# Power_PMIC.net
KiCad netlist of a schematic drawn in Altium Designer
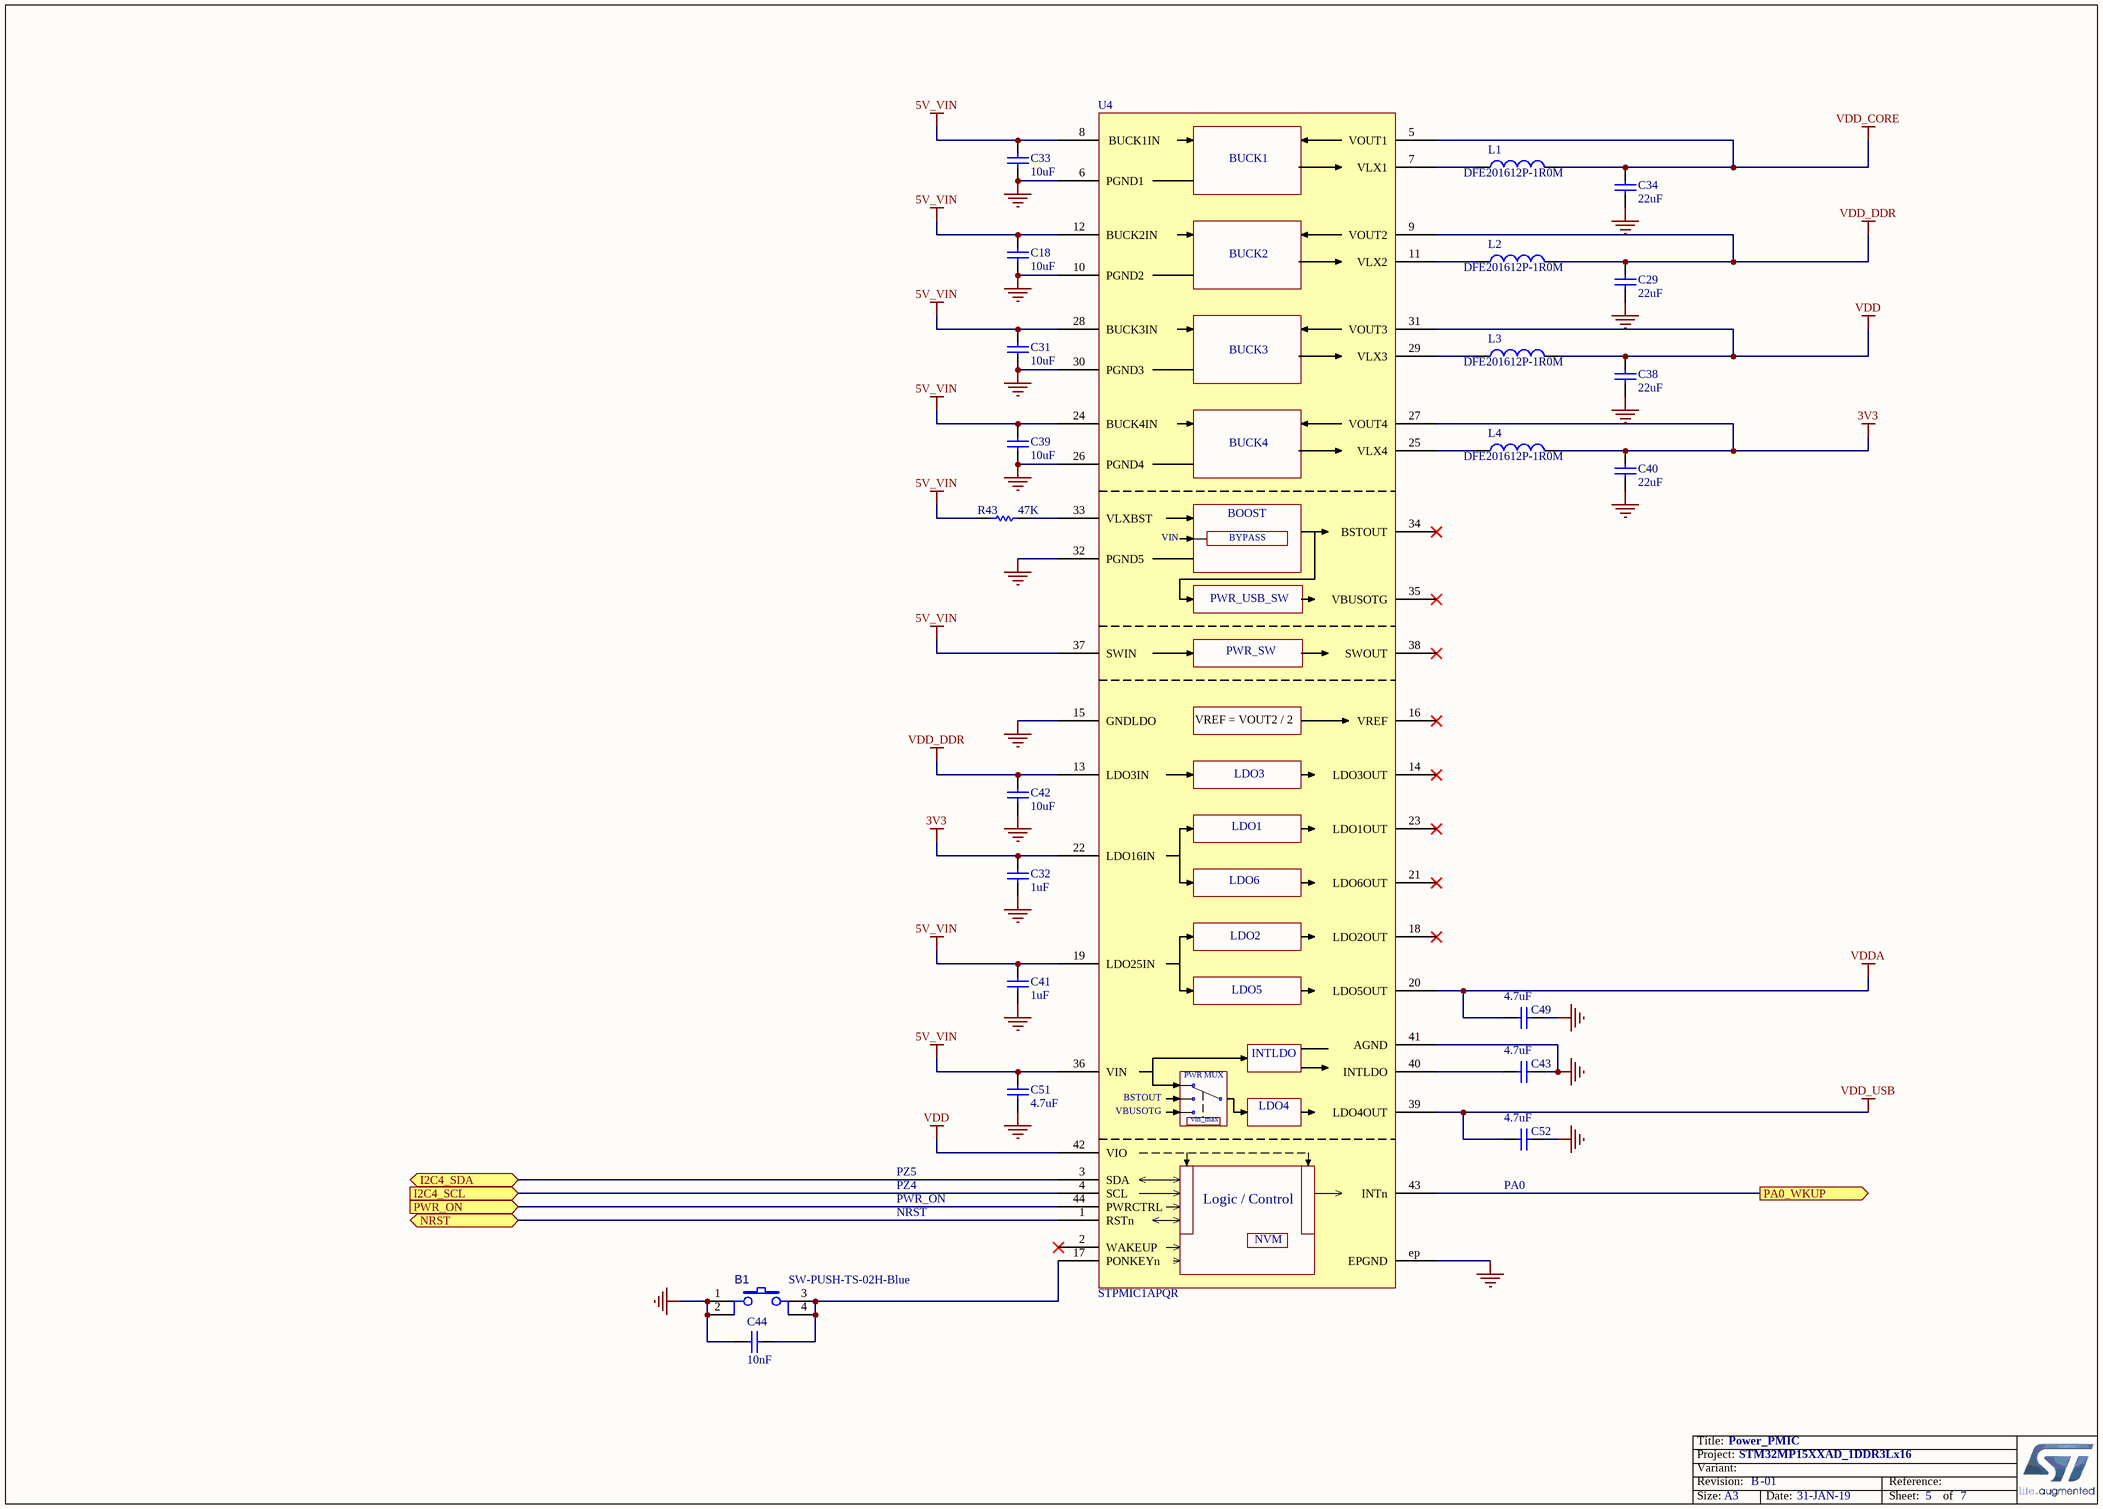
[diagram p0: Power_PMIC.SchDoc]

(export (version "E")
  (design (tool "Eeschema 10.0.6"))
  (components
    (comp (ref "B1")
      (value "SW-PUSH-TS-02H-Blue")
      (footprint "SWI_JIUBABA_C-TS-02H-2-5-B-V-T_R_BLUE")
      (description "Switch HW SMD blue")
      (fields
        (field (name "INTERNAL_PART_NUMBER") "MCD-00172")
        (field (name "MANUFACTURER_PART_NUMBER") "C-TS-02H-2.5-B-V-T/R BLUE")
        (field (name "PROVIDED_BY") "SUBCO")
      )
      (libsource (lib "MCD_PARTS_database") (part "SW-PUSH-TS-02H-Blue"))
    )
    (comp (ref "C18")
      (value "10uF")
      (footprint "C0603")
      (description "Capacitor, MLCC, 10uF, 10V, X5R, 10%, 0603, T=0,8mm")
      (fields
        (field (name "INTERNAL_PART_NUMBER") "MCD-00099")
        (field (name "MANUFACTURER_PART_NUMBER") "GRM188R61A106KE69D")
        (field (name "PROVIDED_BY") "SUBCO")
      )
      (libsource (lib "MCD_PARTS_database") (part "Capacitor"))
    )
    (comp (ref "C29")
      (value "22uF")
      (footprint "C0603")
      (description "Capacitor, MLCC, 22uF, 6V3, X5R, 20%, 0603, T=0,8mm")
      (fields
        (field (name "INTERNAL_PART_NUMBER") "MCD-00100")
        (field (name "MANUFACTURER_PART_NUMBER") "GRM188R60J226MEA0J")
        (field (name "PROVIDED_BY") "SUBCO")
      )
      (libsource (lib "MCD_PARTS_database") (part "Capacitor"))
    )
    (comp (ref "C31")
      (value "10uF")
      (footprint "C0603")
      (description "Capacitor, MLCC, 10uF, 10V, X5R, 10%, 0603, T=0,8mm")
      (fields
        (field (name "INTERNAL_PART_NUMBER") "MCD-00099")
        (field (name "MANUFACTURER_PART_NUMBER") "GRM188R61A106KE69D")
        (field (name "PROVIDED_BY") "SUBCO")
      )
      (libsource (lib "MCD_PARTS_database") (part "Capacitor"))
    )
    (comp (ref "C32")
      (value "1uF")
      (footprint "C0402")
      (description "Capacitor, MLCC, 1uF, 6V3, X5R, 10%, 0402, T=0,5mm")
      (fields
        (field (name "INTERNAL_PART_NUMBER") "MCD-00095")
        (field (name "MANUFACTURER_PART_NUMBER") "GRM155R61E105KA12")
        (field (name "PROVIDED_BY") "SUBCO")
      )
      (libsource (lib "MCD_PARTS_database") (part "Capacitor"))
    )
    (comp (ref "C33")
      (value "10uF")
      (footprint "C0603")
      (description "Capacitor, MLCC, 10uF, 10V, X5R, 10%, 0603, T=0,8mm")
      (fields
        (field (name "INTERNAL_PART_NUMBER") "MCD-00099")
        (field (name "MANUFACTURER_PART_NUMBER") "GRM188R61A106KE69D")
        (field (name "PROVIDED_BY") "SUBCO")
      )
      (libsource (lib "MCD_PARTS_database") (part "Capacitor"))
    )
    (comp (ref "C34")
      (value "22uF")
      (footprint "C0603")
      (description "Capacitor, MLCC, 22uF, 6V3, X5R, 20%, 0603, T=0,8mm")
      (fields
        (field (name "INTERNAL_PART_NUMBER") "MCD-00100")
        (field (name "MANUFACTURER_PART_NUMBER") "GRM188R60J226MEA0J")
        (field (name "PROVIDED_BY") "SUBCO")
      )
      (libsource (lib "MCD_PARTS_database") (part "Capacitor"))
    )
    (comp (ref "C38")
      (value "22uF")
      (footprint "C0603")
      (description "Capacitor, MLCC, 22uF, 6V3, X5R, 20%, 0603, T=0,8mm")
      (fields
        (field (name "INTERNAL_PART_NUMBER") "MCD-00100")
        (field (name "MANUFACTURER_PART_NUMBER") "GRM188R60J226MEA0J")
        (field (name "PROVIDED_BY") "SUBCO")
      )
      (libsource (lib "MCD_PARTS_database") (part "Capacitor"))
    )
    (comp (ref "C39")
      (value "10uF")
      (footprint "C0603")
      (description "Capacitor, MLCC, 10uF, 10V, X5R, 10%, 0603, T=0,8mm")
      (fields
        (field (name "INTERNAL_PART_NUMBER") "MCD-00099")
        (field (name "MANUFACTURER_PART_NUMBER") "GRM188R61A106KE69D")
        (field (name "PROVIDED_BY") "SUBCO")
      )
      (libsource (lib "MCD_PARTS_database") (part "Capacitor"))
    )
    (comp (ref "C40")
      (value "22uF")
      (footprint "C0603")
      (description "Capacitor, MLCC, 22uF, 6V3, X5R, 20%, 0603, T=0,8mm")
      (fields
        (field (name "INTERNAL_PART_NUMBER") "MCD-00100")
        (field (name "MANUFACTURER_PART_NUMBER") "GRM188R60J226MEA0J")
        (field (name "PROVIDED_BY") "SUBCO")
      )
      (libsource (lib "MCD_PARTS_database") (part "Capacitor"))
    )
    (comp (ref "C41")
      (value "1uF")
      (footprint "C0402")
      (description "Capacitor, MLCC, 1uF, 6V3, X5R, 10%, 0402, T=0,5mm")
      (fields
        (field (name "INTERNAL_PART_NUMBER") "MCD-00095")
        (field (name "MANUFACTURER_PART_NUMBER") "GRM155R61E105KA12")
        (field (name "PROVIDED_BY") "SUBCO")
      )
      (libsource (lib "MCD_PARTS_database") (part "Capacitor"))
    )
    (comp (ref "C42")
      (value "10uF")
      (footprint "C0603")
      (description "Capacitor, MLCC, 10uF, 10V, X5R, 10%, 0603, T=0,8mm")
      (fields
        (field (name "INTERNAL_PART_NUMBER") "MCD-00099")
        (field (name "MANUFACTURER_PART_NUMBER") "GRM188R61A106KE69D")
        (field (name "PROVIDED_BY") "SUBCO")
      )
      (libsource (lib "MCD_PARTS_database") (part "Capacitor"))
    )
    (comp (ref "C43")
      (value "4.7uF")
      (footprint "C0402")
      (description "Capacitor, MLCC, 4.7uF, 6V3, X5R, 20%, 0402, T=0,5mm")
      (fields
        (field (name "INTERNAL_PART_NUMBER") "MCD-01356")
        (field (name "MANUFACTURER_PART_NUMBER") "GRM155R60J475ME47")
        (field (name "PROVIDED_BY") "SUBCO")
      )
      (libsource (lib "MCD_PARTS_database") (part "Capacitor"))
    )
    (comp (ref "C44")
      (value "10nF")
      (footprint "C0402")
      (description "Capacitor, MLCC, 10nF, 16V, X7R, 10%, 0402, T=0.5mm")
      (fields
        (field (name "INTERNAL_PART_NUMBER") "MCD-00011")
        (field (name "MANUFACTURER_PART_NUMBER") "CC0402KRX7R7BB103")
        (field (name "PROVIDED_BY") "SUBCO")
      )
      (libsource (lib "MCD_PARTS_database") (part "Capacitor"))
    )
    (comp (ref "C49")
      (value "4.7uF")
      (footprint "C0402")
      (description "Capacitor, MLCC, 4.7uF, 6V3, X5R, 20%, 0402, T=0,5mm")
      (fields
        (field (name "INTERNAL_PART_NUMBER") "MCD-01356")
        (field (name "MANUFACTURER_PART_NUMBER") "GRM155R60J475ME47")
        (field (name "PROVIDED_BY") "SUBCO")
      )
      (libsource (lib "MCD_PARTS_database") (part "Capacitor"))
    )
    (comp (ref "C51")
      (value "4.7uF")
      (footprint "C0402")
      (description "Capacitor, MLCC, 4.7uF, 6V3, X5R, 20%, 0402, T=0,5mm")
      (fields
        (field (name "INTERNAL_PART_NUMBER") "MCD-01356")
        (field (name "MANUFACTURER_PART_NUMBER") "GRM155R60J475ME47")
        (field (name "PROVIDED_BY") "SUBCO")
      )
      (libsource (lib "MCD_PARTS_database") (part "Capacitor"))
    )
    (comp (ref "C52")
      (value "4.7uF")
      (footprint "C0402")
      (description "Capacitor, MLCC, 4.7uF, 6V3, X5R, 20%, 0402, T=0,5mm")
      (fields
        (field (name "INTERNAL_PART_NUMBER") "MCD-01356")
        (field (name "MANUFACTURER_PART_NUMBER") "GRM155R60J475ME47")
        (field (name "PROVIDED_BY") "SUBCO")
      )
      (libsource (lib "MCD_PARTS_database") (part "Capacitor"))
    )
    (comp (ref "L1")
      (value "DFE201612P-1R0M")
      (footprint "IND_MURATA_DFE201612P")
      (description "Inductors 1.0uH 54mOhms3.3A +/-20% 2016")
      (fields
        (field (name "INTERNAL_PART_NUMBER") "MCD-01491")
        (field (name "MANUFACTURER") "MURATA")
        (field (name "PROVIDED_BY") "SUBCO")
      )
      (libsource (lib "MCD_PARTS_database") (part "Inductor"))
    )
    (comp (ref "L2")
      (value "DFE201612P-1R0M")
      (footprint "IND_MURATA_DFE201612P")
      (description "Inductors 1.0uH 54mOhms3.3A +/-20% 2016")
      (fields
        (field (name "INTERNAL_PART_NUMBER") "MCD-01491")
        (field (name "MANUFACTURER") "MURATA")
        (field (name "PROVIDED_BY") "SUBCO")
      )
      (libsource (lib "MCD_PARTS_database") (part "Inductor"))
    )
    (comp (ref "L3")
      (value "DFE201612P-1R0M")
      (footprint "IND_MURATA_DFE201612P")
      (description "Inductors 1.0uH 54mOhms3.3A +/-20% 2016")
      (fields
        (field (name "INTERNAL_PART_NUMBER") "MCD-01491")
        (field (name "MANUFACTURER") "MURATA")
        (field (name "PROVIDED_BY") "SUBCO")
      )
      (libsource (lib "MCD_PARTS_database") (part "Inductor"))
    )
    (comp (ref "L4")
      (value "DFE201612P-1R0M")
      (footprint "IND_MURATA_DFE201612P")
      (description "Inductors 1.0uH 54mOhms3.3A +/-20% 2016")
      (fields
        (field (name "INTERNAL_PART_NUMBER") "MCD-01491")
        (field (name "MANUFACTURER") "MURATA")
        (field (name "PROVIDED_BY") "SUBCO")
      )
      (libsource (lib "MCD_PARTS_database") (part "Inductor"))
    )
    (comp (ref "R43")
      (value "47K")
      (footprint "R0402")
      (description "Resistor,47K,0402,1%,1/16W")
      (fields
        (field (name "INTERNAL_PART_NUMBER") "MCD-00063")
        (field (name "MANUFACTURER_PART_NUMBER") "RC0402FR-0747KL")
        (field (name "PROVIDED_BY") "SUBCO")
      )
      (libsource (lib "MCD_PARTS_database") (part "Resistor"))
    )
    (comp (ref "U4")
      (value "STPMIC1APQR")
      (footprint "ICC_WFQFN44-EPAD_5X6_P040")
      (fields
        (field (name "INTERNAL_PART_NUMBER") "MCD-01650")
        (field (name "MANUFACTURER") "STMICROELECTRONICS")
        (field (name "PROVIDED_BY") "SUBCO with ST control")
      )
      (libsource (lib "MCD_PARTS_database") (part "STPMU1"))
    )
  )
  (nets
    (net (code "1") (name "/I2C4_SCL") (class "Default")
      (node (ref "U4") (pin "4") (pinfunction "SCL_4") (pintype "passive"))
    )
    (net (code "2") (name "/I2C4_SDA") (class "Default")
      (node (ref "U4") (pin "3") (pinfunction "SDA_3") (pintype "passive"))
    )
    (net (code "3") (name "/NRST") (class "Default")
      (node (ref "U4") (pin "1") (pinfunction "RSTn_1") (pintype "passive"))
    )
    (net (code "4") (name "/PA0_WKUP") (class "Default")
      (node (ref "U4") (pin "43") (pinfunction "INTn_43") (pintype "passive"))
    )
    (net (code "5") (name "/PWR_ON") (class "Default")
      (node (ref "U4") (pin "44") (pinfunction "PWRCTRL_44") (pintype "passive"))
    )
    (net (code "6") (name "3V3") (class "Default")
      (node (ref "C32") (pin "2") (pinfunction "2_2") (pintype "passive"))
      (node (ref "C40") (pin "2") (pinfunction "2_2") (pintype "passive"))
      (node (ref "L4") (pin "2") (pinfunction "2_2") (pintype "passive"))
      (node (ref "U4") (pin "22") (pinfunction "LDO16IN_22") (pintype "passive"))
      (node (ref "U4") (pin "27") (pinfunction "VOUT4_27") (pintype "passive"))
    )
    (net (code "7") (name "5V_VIN") (class "Default")
      (node (ref "C18") (pin "2") (pinfunction "2_2") (pintype "passive"))
      (node (ref "C31") (pin "2") (pinfunction "2_2") (pintype "passive"))
      (node (ref "C33") (pin "2") (pinfunction "2_2") (pintype "passive"))
      (node (ref "C39") (pin "2") (pinfunction "2_2") (pintype "passive"))
      (node (ref "C41") (pin "2") (pinfunction "2_2") (pintype "passive"))
      (node (ref "C51") (pin "1") (pinfunction "1_1") (pintype "passive"))
      (node (ref "R43") (pin "2") (pinfunction "2_2") (pintype "passive"))
      (node (ref "U4") (pin "12") (pinfunction "BUCK2IN_12") (pintype "passive"))
      (node (ref "U4") (pin "19") (pinfunction "LDO25IN_19") (pintype "passive"))
      (node (ref "U4") (pin "24") (pinfunction "BUCK4IN_24") (pintype "passive"))
      (node (ref "U4") (pin "28") (pinfunction "BUCK3IN_28") (pintype "passive"))
      (node (ref "U4") (pin "36") (pinfunction "VIN_36") (pintype "passive"))
      (node (ref "U4") (pin "37") (pinfunction "SWIN_37") (pintype "passive"))
      (node (ref "U4") (pin "8") (pinfunction "BUCK1IN_8") (pintype "passive"))
    )
    (net (code "8") (name "GND") (class "Default")
      (node (ref "B1") (pin "1") (pinfunction "1_1") (pintype "passive"))
      (node (ref "B1") (pin "2") (pinfunction "2_2") (pintype "passive"))
      (node (ref "C18") (pin "1") (pinfunction "1_1") (pintype "passive"))
      (node (ref "C29") (pin "1") (pinfunction "1_1") (pintype "passive"))
      (node (ref "C31") (pin "1") (pinfunction "1_1") (pintype "passive"))
      (node (ref "C32") (pin "1") (pinfunction "1_1") (pintype "passive"))
      (node (ref "C33") (pin "1") (pinfunction "1_1") (pintype "passive"))
      (node (ref "C34") (pin "1") (pinfunction "1_1") (pintype "passive"))
      (node (ref "C38") (pin "1") (pinfunction "1_1") (pintype "passive"))
      (node (ref "C39") (pin "1") (pinfunction "1_1") (pintype "passive"))
      (node (ref "C40") (pin "1") (pinfunction "1_1") (pintype "passive"))
      (node (ref "C41") (pin "1") (pinfunction "1_1") (pintype "passive"))
      (node (ref "C42") (pin "1") (pinfunction "1_1") (pintype "passive"))
      (node (ref "C43") (pin "1") (pinfunction "1_1") (pintype "passive"))
      (node (ref "C44") (pin "1") (pinfunction "1_1") (pintype "passive"))
      (node (ref "C49") (pin "1") (pinfunction "1_1") (pintype "passive"))
      (node (ref "C51") (pin "2") (pinfunction "2_2") (pintype "passive"))
      (node (ref "C52") (pin "1") (pinfunction "1_1") (pintype "passive"))
      (node (ref "U4") (pin "10") (pinfunction "PGND2_10") (pintype "passive"))
      (node (ref "U4") (pin "15") (pinfunction "GNDLDO_15") (pintype "passive"))
      (node (ref "U4") (pin "26") (pinfunction "PGND4_26") (pintype "passive"))
      (node (ref "U4") (pin "30") (pinfunction "PGND3_30") (pintype "passive"))
      (node (ref "U4") (pin "32") (pinfunction "PGND5_32") (pintype "passive"))
      (node (ref "U4") (pin "41") (pinfunction "AGND_41") (pintype "passive"))
      (node (ref "U4") (pin "6") (pinfunction "PGND1_6") (pintype "passive"))
      (node (ref "U4") (pin "ep") (pinfunction "EPGND_ep") (pintype "passive"))
    )
    (net (code "9") (name "Net-(U4-INTLDO)") (class "Default")
      (node (ref "C43") (pin "2") (pinfunction "2_2") (pintype "passive"))
      (node (ref "U4") (pin "40") (pinfunction "INTLDO_40") (pintype "passive"))
    )
    (net (code "10") (name "Net-(U4-PONKEYn)") (class "Default")
      (node (ref "B1") (pin "3") (pinfunction "3_3") (pintype "passive"))
      (node (ref "B1") (pin "4") (pinfunction "4_4") (pintype "passive"))
      (node (ref "C44") (pin "2") (pinfunction "2_2") (pintype "passive"))
      (node (ref "U4") (pin "17") (pinfunction "PONKEYn_17") (pintype "passive"))
    )
    (net (code "11") (name "Net-(U4-VLX1)") (class "Default")
      (node (ref "L1") (pin "1") (pinfunction "1_1") (pintype "passive"))
      (node (ref "U4") (pin "7") (pinfunction "VLX1_7") (pintype "passive"))
    )
    (net (code "12") (name "Net-(U4-VLX2)") (class "Default")
      (node (ref "L2") (pin "1") (pinfunction "1_1") (pintype "passive"))
      (node (ref "U4") (pin "11") (pinfunction "VLX2_11") (pintype "passive"))
    )
    (net (code "13") (name "Net-(U4-VLX3)") (class "Default")
      (node (ref "L3") (pin "1") (pinfunction "1_1") (pintype "passive"))
      (node (ref "U4") (pin "29") (pinfunction "VLX3_29") (pintype "passive"))
    )
    (net (code "14") (name "Net-(U4-VLX4)") (class "Default")
      (node (ref "L4") (pin "1") (pinfunction "1_1") (pintype "passive"))
      (node (ref "U4") (pin "25") (pinfunction "VLX4_25") (pintype "passive"))
    )
    (net (code "15") (name "Net-(U4-VLXBST)") (class "Default")
      (node (ref "R43") (pin "1") (pinfunction "1_1") (pintype "passive"))
      (node (ref "U4") (pin "33") (pinfunction "VLXBST_33") (pintype "passive"))
    )
    (net (code "16") (name "VDD") (class "Default")
      (node (ref "C38") (pin "2") (pinfunction "2_2") (pintype "passive"))
      (node (ref "L3") (pin "2") (pinfunction "2_2") (pintype "passive"))
      (node (ref "U4") (pin "31") (pinfunction "VOUT3_31") (pintype "passive"))
      (node (ref "U4") (pin "42") (pinfunction "VIO_42") (pintype "passive"))
    )
    (net (code "17") (name "VDDA") (class "Default")
      (node (ref "C49") (pin "2") (pinfunction "2_2") (pintype "passive"))
      (node (ref "U4") (pin "20") (pinfunction "LDO5OUT_20") (pintype "passive"))
    )
    (net (code "18") (name "VDD_CORE") (class "Default")
      (node (ref "C34") (pin "2") (pinfunction "2_2") (pintype "passive"))
      (node (ref "L1") (pin "2") (pinfunction "2_2") (pintype "passive"))
      (node (ref "U4") (pin "5") (pinfunction "VOUT1_5") (pintype "passive"))
    )
    (net (code "19") (name "VDD_DDR") (class "Default")
      (node (ref "C29") (pin "2") (pinfunction "2_2") (pintype "passive"))
      (node (ref "C42") (pin "2") (pinfunction "2_2") (pintype "passive"))
      (node (ref "L2") (pin "2") (pinfunction "2_2") (pintype "passive"))
      (node (ref "U4") (pin "13") (pinfunction "LDO3IN_13") (pintype "passive"))
      (node (ref "U4") (pin "9") (pinfunction "VOUT2_9") (pintype "passive"))
    )
    (net (code "20") (name "VDD_USB") (class "Default")
      (node (ref "C52") (pin "2") (pinfunction "2_2") (pintype "passive"))
      (node (ref "U4") (pin "39") (pinfunction "LDO4OUT_39") (pintype "passive"))
    )
    (net (code "21") (name "unconnected-(U4-BSTOUT-Pad34)") (class "Default")
      (node (ref "U4") (pin "34") (pinfunction "BSTOUT_34") (pintype "passive+no_connect"))
    )
    (net (code "22") (name "unconnected-(U4-LDO1OUT-Pad23)") (class "Default")
      (node (ref "U4") (pin "23") (pinfunction "LDO1OUT_23") (pintype "passive+no_connect"))
    )
    (net (code "23") (name "unconnected-(U4-LDO2OUT-Pad18)") (class "Default")
      (node (ref "U4") (pin "18") (pinfunction "LDO2OUT_18") (pintype "passive+no_connect"))
    )
    (net (code "24") (name "unconnected-(U4-LDO3OUT-Pad14)") (class "Default")
      (node (ref "U4") (pin "14") (pinfunction "LDO3OUT_14") (pintype "passive+no_connect"))
    )
    (net (code "25") (name "unconnected-(U4-LDO6OUT-Pad21)") (class "Default")
      (node (ref "U4") (pin "21") (pinfunction "LDO6OUT_21") (pintype "passive+no_connect"))
    )
    (net (code "26") (name "unconnected-(U4-SWOUT-Pad38)") (class "Default")
      (node (ref "U4") (pin "38") (pinfunction "SWOUT_38") (pintype "passive+no_connect"))
    )
    (net (code "27") (name "unconnected-(U4-VBUSOTG-Pad35)") (class "Default")
      (node (ref "U4") (pin "35") (pinfunction "VBUSOTG_35") (pintype "passive+no_connect"))
    )
    (net (code "28") (name "unconnected-(U4-VREF-Pad16)") (class "Default")
      (node (ref "U4") (pin "16") (pinfunction "VREF_16") (pintype "passive+no_connect"))
    )
    (net (code "29") (name "unconnected-(U4-WAKEUP-Pad2)") (class "Default")
      (node (ref "U4") (pin "2") (pinfunction "WAKEUP_2") (pintype "passive+no_connect"))
    )
  )
)
